# main.net
KiCad netlist of a schematic drawn in EAGLE
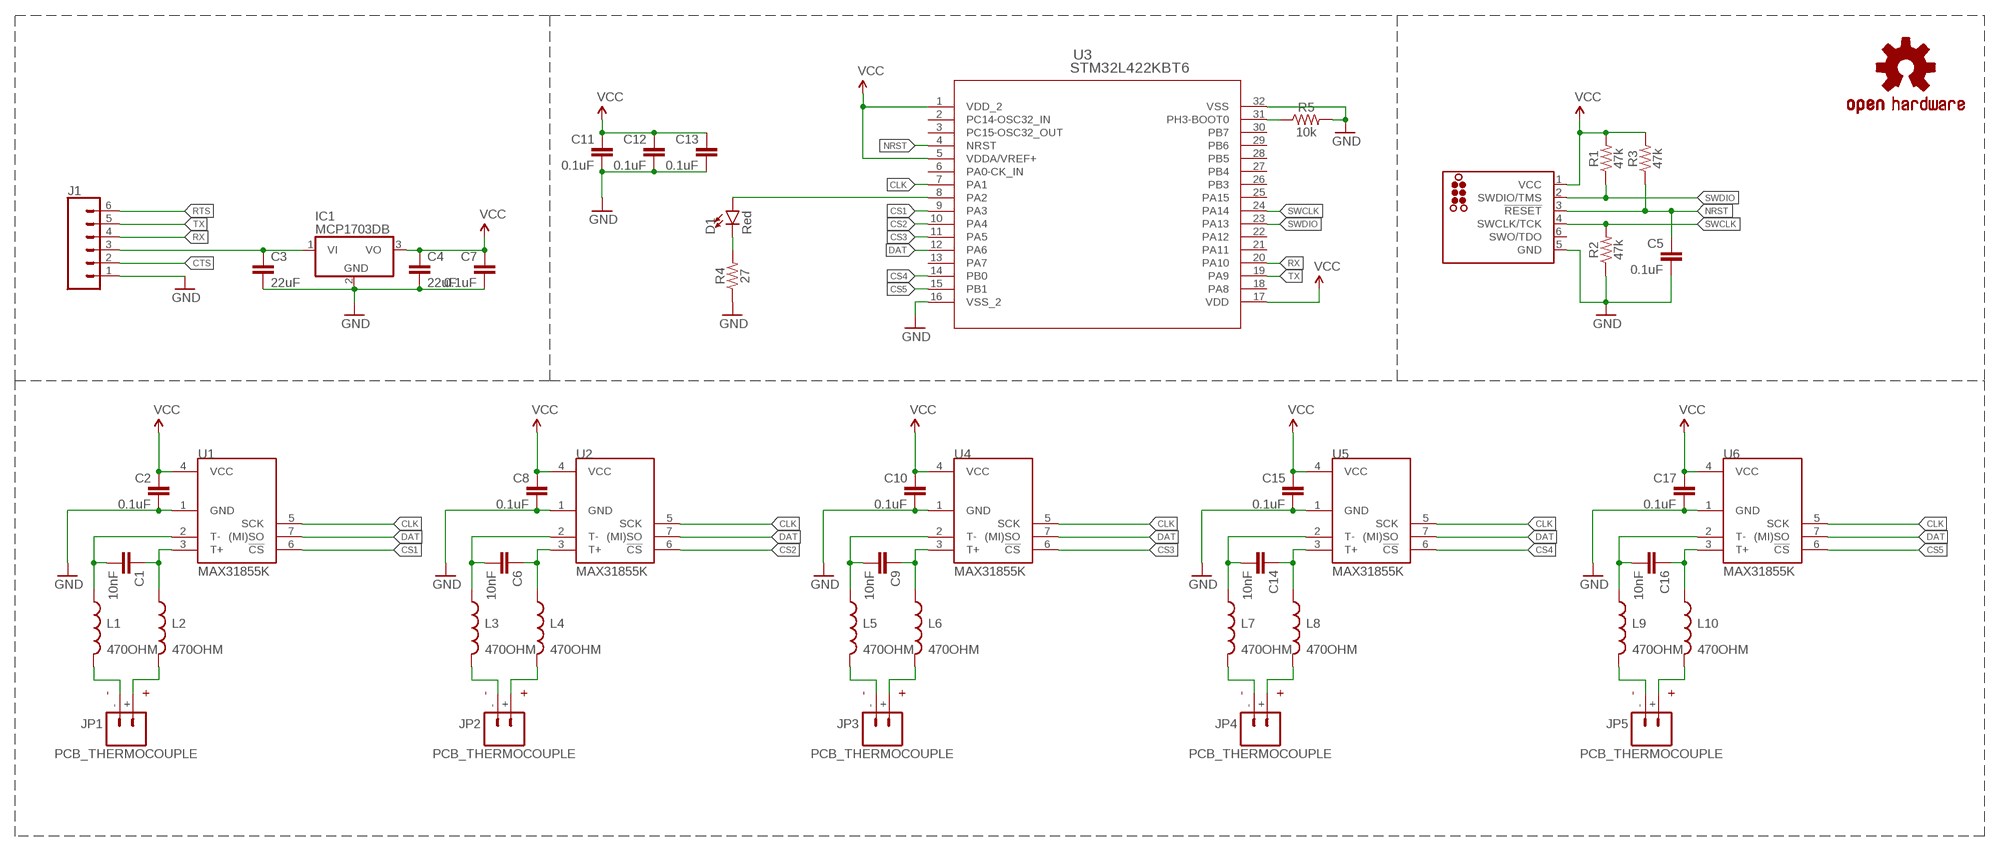
[diagram p0: schematic, sheet 1]

(export (version "E")
  (design (tool "Eeschema 10.0.6"))
  (components
    (comp (ref "C1")
      (value "10nF")
      (footprint "eagle-import:0603-CAP")
      (libsource (lib "eagle-import") (part "10NF/10000PF-50V-10%(0603)"))
    )
    (comp (ref "C2")
      (value "0.1uF")
      (footprint "eagle-import:0603-CAP")
      (libsource (lib "eagle-import") (part "0.1UF-25V(+80/-20%)(0603)"))
    )
    (comp (ref "C3")
      (value "22uF")
      (footprint "eagle-import:0603")
      (libsource (lib "eagle-import") (part "22UF-0603-6.3V-20%"))
    )
    (comp (ref "C4")
      (value "22uF")
      (footprint "eagle-import:0603")
      (libsource (lib "eagle-import") (part "22UF-0603-6.3V-20%"))
    )
    (comp (ref "C5")
      (value "0.1uF")
      (footprint "eagle-import:0603-CAP")
      (libsource (lib "eagle-import") (part "0.1UF-25V(+80/-20%)(0603)"))
    )
    (comp (ref "C6")
      (value "10nF")
      (footprint "eagle-import:0603-CAP")
      (libsource (lib "eagle-import") (part "10NF/10000PF-50V-10%(0603)"))
    )
    (comp (ref "C7")
      (value "0.1uF")
      (footprint "eagle-import:0603-CAP")
      (libsource (lib "eagle-import") (part "0.1UF-25V(+80/-20%)(0603)"))
    )
    (comp (ref "C8")
      (value "0.1uF")
      (footprint "eagle-import:0603-CAP")
      (libsource (lib "eagle-import") (part "0.1UF-25V(+80/-20%)(0603)"))
    )
    (comp (ref "C9")
      (value "10nF")
      (footprint "eagle-import:0603-CAP")
      (libsource (lib "eagle-import") (part "10NF/10000PF-50V-10%(0603)"))
    )
    (comp (ref "C10")
      (value "0.1uF")
      (footprint "eagle-import:0603-CAP")
      (libsource (lib "eagle-import") (part "0.1UF-25V(+80/-20%)(0603)"))
    )
    (comp (ref "C11")
      (value "0.1uF")
      (footprint "eagle-import:0603-CAP")
      (libsource (lib "eagle-import") (part "0.1UF-25V(+80/-20%)(0603)"))
    )
    (comp (ref "C12")
      (value "0.1uF")
      (footprint "eagle-import:0603-CAP")
      (libsource (lib "eagle-import") (part "0.1UF-25V(+80/-20%)(0603)"))
    )
    (comp (ref "C13")
      (value "0.1uF")
      (footprint "eagle-import:0603-CAP")
      (libsource (lib "eagle-import") (part "0.1UF-25V(+80/-20%)(0603)"))
    )
    (comp (ref "C14")
      (value "10nF")
      (footprint "eagle-import:0603-CAP")
      (libsource (lib "eagle-import") (part "10NF/10000PF-50V-10%(0603)"))
    )
    (comp (ref "C15")
      (value "0.1uF")
      (footprint "eagle-import:0603-CAP")
      (libsource (lib "eagle-import") (part "0.1UF-25V(+80/-20%)(0603)"))
    )
    (comp (ref "C16")
      (value "10nF")
      (footprint "eagle-import:0603-CAP")
      (libsource (lib "eagle-import") (part "10NF/10000PF-50V-10%(0603)"))
    )
    (comp (ref "C17")
      (value "0.1uF")
      (footprint "eagle-import:0603-CAP")
      (libsource (lib "eagle-import") (part "0.1UF-25V(+80/-20%)(0603)"))
    )
    (comp (ref "D1")
      (value "Red")
      (footprint "eagle-import:LED-0603")
      (libsource (lib "eagle-import") (part "LED-RED-0603-WE"))
    )
    (comp (ref "IC1")
      (value "MCP1703DB")
      (footprint "eagle-import:SOT223")
      (libsource (lib "eagle-import") (part "MCP1703DB"))
    )
    (comp (ref "J1")
      (value "CONN_06NO_SILK_NO_POP")
      (footprint "eagle-import:1X06_NO_SILK")
      (libsource (lib "eagle-import") (part "CONN_06NO_SILK_NO_POP"))
    )
    (comp (ref "J2")
      (value "TC2030_SWD-MCP-NL")
      (footprint "eagle-import:TC2030-MCP-NL")
      (libsource (lib "eagle-import") (part "TC2030_SWD-MCP-NL"))
    )
    (comp (ref "JP1")
      (value "PCB_THERMOCOUPLE")
      (footprint "eagle-import:PCC-SMP")
      (libsource (lib "eagle-import") (part "PCB_THERMOCOUPLE"))
    )
    (comp (ref "JP2")
      (value "PCB_THERMOCOUPLE")
      (footprint "eagle-import:PCC-SMP")
      (libsource (lib "eagle-import") (part "PCB_THERMOCOUPLE"))
    )
    (comp (ref "JP3")
      (value "PCB_THERMOCOUPLE")
      (footprint "eagle-import:PCC-SMP")
      (libsource (lib "eagle-import") (part "PCB_THERMOCOUPLE"))
    )
    (comp (ref "JP4")
      (value "PCB_THERMOCOUPLE")
      (footprint "eagle-import:PCC-SMP")
      (libsource (lib "eagle-import") (part "PCB_THERMOCOUPLE"))
    )
    (comp (ref "JP5")
      (value "PCB_THERMOCOUPLE")
      (footprint "eagle-import:PCC-SMP")
      (libsource (lib "eagle-import") (part "PCB_THERMOCOUPLE"))
    )
    (comp (ref "L1")
      (value "470OHM")
      (footprint "eagle-import:0603")
      (libsource (lib "eagle-import") (part "INDUCTOR0603"))
    )
    (comp (ref "L2")
      (value "470OHM")
      (footprint "eagle-import:0603")
      (libsource (lib "eagle-import") (part "INDUCTOR0603"))
    )
    (comp (ref "L3")
      (value "470OHM")
      (footprint "eagle-import:0603")
      (libsource (lib "eagle-import") (part "INDUCTOR0603"))
    )
    (comp (ref "L4")
      (value "470OHM")
      (footprint "eagle-import:0603")
      (libsource (lib "eagle-import") (part "INDUCTOR0603"))
    )
    (comp (ref "L5")
      (value "470OHM")
      (footprint "eagle-import:0603")
      (libsource (lib "eagle-import") (part "INDUCTOR0603"))
    )
    (comp (ref "L6")
      (value "470OHM")
      (footprint "eagle-import:0603")
      (libsource (lib "eagle-import") (part "INDUCTOR0603"))
    )
    (comp (ref "L7")
      (value "470OHM")
      (footprint "eagle-import:0603")
      (libsource (lib "eagle-import") (part "INDUCTOR0603"))
    )
    (comp (ref "L8")
      (value "470OHM")
      (footprint "eagle-import:0603")
      (libsource (lib "eagle-import") (part "INDUCTOR0603"))
    )
    (comp (ref "L9")
      (value "470OHM")
      (footprint "eagle-import:0603")
      (libsource (lib "eagle-import") (part "INDUCTOR0603"))
    )
    (comp (ref "L10")
      (value "470OHM")
      (footprint "eagle-import:0603")
      (libsource (lib "eagle-import") (part "INDUCTOR0603"))
    )
    (comp (ref "LOGO1")
      (value "OSHW-LOGOL")
      (footprint "eagle-import:OSHW-LOGO-L")
      (libsource (lib "eagle-import") (part "OSHW-LOGOL"))
    )
    (comp (ref "R1")
      (value "47k")
      (footprint "eagle-import:0603")
      (libsource (lib "eagle-import") (part "47KOHM-0603-1/10W-1%"))
    )
    (comp (ref "R2")
      (value "47k")
      (footprint "eagle-import:0603")
      (libsource (lib "eagle-import") (part "47KOHM-0603-1/10W-1%"))
    )
    (comp (ref "R3")
      (value "47k")
      (footprint "eagle-import:0603")
      (libsource (lib "eagle-import") (part "47KOHM-0603-1/10W-1%"))
    )
    (comp (ref "R4")
      (value "27")
      (footprint "eagle-import:0603")
      (libsource (lib "eagle-import") (part "27OHM-0603-1/10W-1%"))
    )
    (comp (ref "R5")
      (value "10k")
      (footprint "eagle-import:0603")
      (libsource (lib "eagle-import") (part "10KOHM-0603-1/10W-1%"))
    )
    (comp (ref "U1")
      (value "MAX31855K")
      (footprint "eagle-import:SOIC8")
      (libsource (lib "eagle-import") (part "MAX31855K"))
    )
    (comp (ref "U2")
      (value "MAX31855K")
      (footprint "eagle-import:SOIC8")
      (libsource (lib "eagle-import") (part "MAX31855K"))
    )
    (comp (ref "U3")
      (value "STM32L422KBT6")
      (footprint "eagle-import:LQFP_422KBT6_STM")
      (fields (field (name "COPYRIGHT") "Copyright (C) 2023 Ultra Librarian. All rights reserved."))
      (libsource (lib "eagle-import") (part "STM32L422KBT6"))
    )
    (comp (ref "U4")
      (value "MAX31855K")
      (footprint "eagle-import:SOIC8")
      (libsource (lib "eagle-import") (part "MAX31855K"))
    )
    (comp (ref "U5")
      (value "MAX31855K")
      (footprint "eagle-import:SOIC8")
      (libsource (lib "eagle-import") (part "MAX31855K"))
    )
    (comp (ref "U6")
      (value "MAX31855K")
      (footprint "eagle-import:SOIC8")
      (libsource (lib "eagle-import") (part "MAX31855K"))
    )
  )
  (nets
    (net (code "1") (name "CLK") (class "Default")
      (node (ref "U1") (pin "5") (pinfunction "SCK_5") (pintype "bidirectional"))
      (node (ref "U2") (pin "5") (pinfunction "SCK_5") (pintype "bidirectional"))
      (node (ref "U3") (pin "7") (pinfunction "PA1_7") (pintype "bidirectional"))
      (node (ref "U4") (pin "5") (pinfunction "SCK_5") (pintype "bidirectional"))
      (node (ref "U5") (pin "5") (pinfunction "SCK_5") (pintype "bidirectional"))
      (node (ref "U6") (pin "5") (pinfunction "SCK_5") (pintype "bidirectional"))
    )
    (net (code "2") (name "CS1") (class "Default")
      (node (ref "U1") (pin "6") (pinfunction "~{CS}_6") (pintype "bidirectional"))
      (node (ref "U3") (pin "9") (pinfunction "PA3_9") (pintype "bidirectional"))
    )
    (net (code "3") (name "CS2") (class "Default")
      (node (ref "U2") (pin "6") (pinfunction "~{CS}_6") (pintype "bidirectional"))
      (node (ref "U3") (pin "10") (pinfunction "PA4_10") (pintype "bidirectional"))
    )
    (net (code "4") (name "CS3") (class "Default")
      (node (ref "U3") (pin "11") (pinfunction "PA5_11") (pintype "bidirectional"))
      (node (ref "U4") (pin "6") (pinfunction "~{CS}_6") (pintype "bidirectional"))
    )
    (net (code "5") (name "CS4") (class "Default")
      (node (ref "U3") (pin "14") (pinfunction "PB0_14") (pintype "bidirectional"))
      (node (ref "U5") (pin "6") (pinfunction "~{CS}_6") (pintype "bidirectional"))
    )
    (net (code "6") (name "CS5") (class "Default")
      (node (ref "U3") (pin "15") (pinfunction "PB1_15") (pintype "bidirectional"))
      (node (ref "U6") (pin "6") (pinfunction "~{CS}_6") (pintype "bidirectional"))
    )
    (net (code "7") (name "CTS") (class "Default")
      (node (ref "J1") (pin "2") (pinfunction "2_2") (pintype "passive"))
    )
    (net (code "8") (name "DAT") (class "Default")
      (node (ref "U1") (pin "7") (pinfunction "(MI)SO_7") (pintype "bidirectional"))
      (node (ref "U2") (pin "7") (pinfunction "(MI)SO_7") (pintype "bidirectional"))
      (node (ref "U3") (pin "12") (pinfunction "PA6_12") (pintype "bidirectional"))
      (node (ref "U4") (pin "7") (pinfunction "(MI)SO_7") (pintype "bidirectional"))
      (node (ref "U5") (pin "7") (pinfunction "(MI)SO_7") (pintype "bidirectional"))
      (node (ref "U6") (pin "7") (pinfunction "(MI)SO_7") (pintype "bidirectional"))
    )
    (net (code "9") (name "GND") (class "Default")
      (node (ref "C10") (pin "2") (pinfunction "2_2") (pintype "passive"))
      (node (ref "C11") (pin "2") (pinfunction "2_2") (pintype "passive"))
      (node (ref "C12") (pin "2") (pinfunction "2_2") (pintype "passive"))
      (node (ref "C13") (pin "2") (pinfunction "2_2") (pintype "passive"))
      (node (ref "C15") (pin "2") (pinfunction "2_2") (pintype "passive"))
      (node (ref "C17") (pin "2") (pinfunction "2_2") (pintype "passive"))
      (node (ref "C2") (pin "2") (pinfunction "2_2") (pintype "passive"))
      (node (ref "C3") (pin "2") (pinfunction "2_2") (pintype "passive"))
      (node (ref "C4") (pin "2") (pinfunction "2_2") (pintype "passive"))
      (node (ref "C5") (pin "2") (pinfunction "2_2") (pintype "passive"))
      (node (ref "C7") (pin "2") (pinfunction "2_2") (pintype "passive"))
      (node (ref "C8") (pin "2") (pinfunction "2_2") (pintype "passive"))
      (node (ref "IC1") (pin "2") (pinfunction "GND_2") (pintype "passive"))
      (node (ref "J1") (pin "1") (pinfunction "1_1") (pintype "passive"))
      (node (ref "J2") (pin "5") (pinfunction "GND_5") (pintype "passive"))
      (node (ref "R2") (pin "1") (pinfunction "1_1") (pintype "passive"))
      (node (ref "R4") (pin "1") (pinfunction "1_1") (pintype "passive"))
      (node (ref "R5") (pin "2") (pinfunction "2_2") (pintype "passive"))
      (node (ref "U1") (pin "1") (pinfunction "GND_1") (pintype "bidirectional"))
      (node (ref "U2") (pin "1") (pinfunction "GND_1") (pintype "bidirectional"))
      (node (ref "U3") (pin "16") (pinfunction "VSS_2_16") (pintype "passive"))
      (node (ref "U3") (pin "32") (pinfunction "VSS_32") (pintype "passive"))
      (node (ref "U4") (pin "1") (pinfunction "GND_1") (pintype "bidirectional"))
      (node (ref "U5") (pin "1") (pinfunction "GND_1") (pintype "bidirectional"))
      (node (ref "U6") (pin "1") (pinfunction "GND_1") (pintype "bidirectional"))
    )
    (net (code "10") (name "NRST") (class "Default")
      (node (ref "C5") (pin "1") (pinfunction "1_1") (pintype "passive"))
      (node (ref "J2") (pin "3") (pinfunction "~{RESET}_3") (pintype "output"))
      (node (ref "R3") (pin "1") (pinfunction "1_1") (pintype "passive"))
      (node (ref "U3") (pin "4") (pinfunction "NRST_4") (pintype "passive"))
    )
    (net (code "11") (name "Net-(D1-PadC)") (class "Default")
      (node (ref "D1") (pin "C") (pinfunction "C_C") (pintype "passive"))
      (node (ref "R4") (pin "2") (pinfunction "2_2") (pintype "passive"))
    )
    (net (code "12") (name "Net-(IC1-VI)") (class "Default")
      (node (ref "C3") (pin "1") (pinfunction "1_1") (pintype "passive"))
      (node (ref "IC1") (pin "1") (pinfunction "VI_1") (pintype "input"))
      (node (ref "J1") (pin "3") (pinfunction "3_3") (pintype "passive"))
    )
    (net (code "13") (name "Net-(JP1-Pad+)") (class "Default")
      (node (ref "JP1") (pin "+") (pinfunction "+_+") (pintype "passive"))
      (node (ref "L2") (pin "2") (pinfunction "2_2") (pintype "passive"))
    )
    (net (code "14") (name "Net-(JP1-Pad-)") (class "Default")
      (node (ref "JP1") (pin "-") (pinfunction "-_-") (pintype "passive"))
      (node (ref "L1") (pin "2") (pinfunction "2_2") (pintype "passive"))
    )
    (net (code "15") (name "Net-(JP2-Pad+)") (class "Default")
      (node (ref "JP2") (pin "+") (pinfunction "+_+") (pintype "passive"))
      (node (ref "L4") (pin "2") (pinfunction "2_2") (pintype "passive"))
    )
    (net (code "16") (name "Net-(JP2-Pad-)") (class "Default")
      (node (ref "JP2") (pin "-") (pinfunction "-_-") (pintype "passive"))
      (node (ref "L3") (pin "2") (pinfunction "2_2") (pintype "passive"))
    )
    (net (code "17") (name "Net-(JP3-Pad+)") (class "Default")
      (node (ref "JP3") (pin "+") (pinfunction "+_+") (pintype "passive"))
      (node (ref "L6") (pin "2") (pinfunction "2_2") (pintype "passive"))
    )
    (net (code "18") (name "Net-(JP3-Pad-)") (class "Default")
      (node (ref "JP3") (pin "-") (pinfunction "-_-") (pintype "passive"))
      (node (ref "L5") (pin "2") (pinfunction "2_2") (pintype "passive"))
    )
    (net (code "19") (name "Net-(JP4-Pad+)") (class "Default")
      (node (ref "JP4") (pin "+") (pinfunction "+_+") (pintype "passive"))
      (node (ref "L8") (pin "2") (pinfunction "2_2") (pintype "passive"))
    )
    (net (code "20") (name "Net-(JP4-Pad-)") (class "Default")
      (node (ref "JP4") (pin "-") (pinfunction "-_-") (pintype "passive"))
      (node (ref "L7") (pin "2") (pinfunction "2_2") (pintype "passive"))
    )
    (net (code "21") (name "Net-(JP5-Pad+)") (class "Default")
      (node (ref "JP5") (pin "+") (pinfunction "+_+") (pintype "passive"))
      (node (ref "L10") (pin "2") (pinfunction "2_2") (pintype "passive"))
    )
    (net (code "22") (name "Net-(JP5-Pad-)") (class "Default")
      (node (ref "JP5") (pin "-") (pinfunction "-_-") (pintype "passive"))
      (node (ref "L9") (pin "2") (pinfunction "2_2") (pintype "passive"))
    )
    (net (code "23") (name "Net-(U1-T+)") (class "Default")
      (node (ref "C1") (pin "1") (pinfunction "1_1") (pintype "passive"))
      (node (ref "L2") (pin "1") (pinfunction "1_1") (pintype "passive"))
      (node (ref "U1") (pin "3") (pinfunction "T+_3") (pintype "bidirectional"))
    )
    (net (code "24") (name "Net-(U1-T-)") (class "Default")
      (node (ref "C1") (pin "2") (pinfunction "2_2") (pintype "passive"))
      (node (ref "L1") (pin "1") (pinfunction "1_1") (pintype "passive"))
      (node (ref "U1") (pin "2") (pinfunction "T-_2") (pintype "bidirectional"))
    )
    (net (code "25") (name "Net-(U2-T+)") (class "Default")
      (node (ref "C6") (pin "1") (pinfunction "1_1") (pintype "passive"))
      (node (ref "L4") (pin "1") (pinfunction "1_1") (pintype "passive"))
      (node (ref "U2") (pin "3") (pinfunction "T+_3") (pintype "bidirectional"))
    )
    (net (code "26") (name "Net-(U2-T-)") (class "Default")
      (node (ref "C6") (pin "2") (pinfunction "2_2") (pintype "passive"))
      (node (ref "L3") (pin "1") (pinfunction "1_1") (pintype "passive"))
      (node (ref "U2") (pin "2") (pinfunction "T-_2") (pintype "bidirectional"))
    )
    (net (code "27") (name "Net-(U3-PA2)") (class "Default")
      (node (ref "D1") (pin "A") (pinfunction "A_A") (pintype "passive"))
      (node (ref "U3") (pin "8") (pinfunction "PA2_8") (pintype "bidirectional"))
    )
    (net (code "28") (name "Net-(U3-PH3-BOOT0)") (class "Default")
      (node (ref "R5") (pin "1") (pinfunction "1_1") (pintype "passive"))
      (node (ref "U3") (pin "31") (pinfunction "PH3-BOOT0_31") (pintype "passive"))
    )
    (net (code "29") (name "Net-(U4-T+)") (class "Default")
      (node (ref "C9") (pin "1") (pinfunction "1_1") (pintype "passive"))
      (node (ref "L6") (pin "1") (pinfunction "1_1") (pintype "passive"))
      (node (ref "U4") (pin "3") (pinfunction "T+_3") (pintype "bidirectional"))
    )
    (net (code "30") (name "Net-(U4-T-)") (class "Default")
      (node (ref "C9") (pin "2") (pinfunction "2_2") (pintype "passive"))
      (node (ref "L5") (pin "1") (pinfunction "1_1") (pintype "passive"))
      (node (ref "U4") (pin "2") (pinfunction "T-_2") (pintype "bidirectional"))
    )
    (net (code "31") (name "Net-(U5-T+)") (class "Default")
      (node (ref "C14") (pin "1") (pinfunction "1_1") (pintype "passive"))
      (node (ref "L8") (pin "1") (pinfunction "1_1") (pintype "passive"))
      (node (ref "U5") (pin "3") (pinfunction "T+_3") (pintype "bidirectional"))
    )
    (net (code "32") (name "Net-(U5-T-)") (class "Default")
      (node (ref "C14") (pin "2") (pinfunction "2_2") (pintype "passive"))
      (node (ref "L7") (pin "1") (pinfunction "1_1") (pintype "passive"))
      (node (ref "U5") (pin "2") (pinfunction "T-_2") (pintype "bidirectional"))
    )
    (net (code "33") (name "Net-(U6-T+)") (class "Default")
      (node (ref "C16") (pin "1") (pinfunction "1_1") (pintype "passive"))
      (node (ref "L10") (pin "1") (pinfunction "1_1") (pintype "passive"))
      (node (ref "U6") (pin "3") (pinfunction "T+_3") (pintype "bidirectional"))
    )
    (net (code "34") (name "Net-(U6-T-)") (class "Default")
      (node (ref "C16") (pin "2") (pinfunction "2_2") (pintype "passive"))
      (node (ref "L9") (pin "1") (pinfunction "1_1") (pintype "passive"))
      (node (ref "U6") (pin "2") (pinfunction "T-_2") (pintype "bidirectional"))
    )
    (net (code "35") (name "RTS") (class "Default")
      (node (ref "J1") (pin "6") (pinfunction "6_6") (pintype "passive"))
    )
    (net (code "36") (name "RX") (class "Default")
      (node (ref "J1") (pin "4") (pinfunction "4_4") (pintype "passive"))
      (node (ref "U3") (pin "20") (pinfunction "PA10_20") (pintype "bidirectional"))
    )
    (net (code "37") (name "SWCLK") (class "Default")
      (node (ref "J2") (pin "4") (pinfunction "SWCLK/TCK_4") (pintype "output"))
      (node (ref "R2") (pin "2") (pinfunction "2_2") (pintype "passive"))
      (node (ref "U3") (pin "24") (pinfunction "PA14_24") (pintype "bidirectional"))
    )
    (net (code "38") (name "SWDIO") (class "Default")
      (node (ref "J2") (pin "2") (pinfunction "SWDIO/TMS_2") (pintype "bidirectional"))
      (node (ref "R1") (pin "1") (pinfunction "1_1") (pintype "passive"))
      (node (ref "U3") (pin "23") (pinfunction "PA13_23") (pintype "bidirectional"))
    )
    (net (code "39") (name "TX") (class "Default")
      (node (ref "J1") (pin "5") (pinfunction "5_5") (pintype "passive"))
      (node (ref "U3") (pin "19") (pinfunction "PA9_19") (pintype "bidirectional"))
    )
    (net (code "40") (name "VCC") (class "Default")
      (node (ref "C10") (pin "1") (pinfunction "1_1") (pintype "passive"))
      (node (ref "C11") (pin "1") (pinfunction "1_1") (pintype "passive"))
      (node (ref "C12") (pin "1") (pinfunction "1_1") (pintype "passive"))
      (node (ref "C13") (pin "1") (pinfunction "1_1") (pintype "passive"))
      (node (ref "C15") (pin "1") (pinfunction "1_1") (pintype "passive"))
      (node (ref "C17") (pin "1") (pinfunction "1_1") (pintype "passive"))
      (node (ref "C2") (pin "1") (pinfunction "1_1") (pintype "passive"))
      (node (ref "C4") (pin "1") (pinfunction "1_1") (pintype "passive"))
      (node (ref "C7") (pin "1") (pinfunction "1_1") (pintype "passive"))
      (node (ref "C8") (pin "1") (pinfunction "1_1") (pintype "passive"))
      (node (ref "IC1") (pin "3") (pinfunction "VO_3") (pintype "passive"))
      (node (ref "J2") (pin "1") (pinfunction "VCC_1") (pintype "passive"))
      (node (ref "R1") (pin "2") (pinfunction "2_2") (pintype "passive"))
      (node (ref "R3") (pin "2") (pinfunction "2_2") (pintype "passive"))
      (node (ref "U1") (pin "4") (pinfunction "VCC_4") (pintype "bidirectional"))
      (node (ref "U2") (pin "4") (pinfunction "VCC_4") (pintype "bidirectional"))
      (node (ref "U3") (pin "1") (pinfunction "VDD_2_1") (pintype "power_in"))
      (node (ref "U3") (pin "17") (pinfunction "VDD_17") (pintype "power_in"))
      (node (ref "U3") (pin "5") (pinfunction "VDDA/VREF+_5") (pintype "power_in"))
      (node (ref "U4") (pin "4") (pinfunction "VCC_4") (pintype "bidirectional"))
      (node (ref "U5") (pin "4") (pinfunction "VCC_4") (pintype "bidirectional"))
      (node (ref "U6") (pin "4") (pinfunction "VCC_4") (pintype "bidirectional"))
    )
    (net (code "41") (name "unconnected-(J2-SWO{slash}TDO-Pad6)") (class "Default")
      (node (ref "J2") (pin "6") (pinfunction "SWO/TDO_6") (pintype "bidirectional"))
    )
    (net (code "42") (name "unconnected-(U3-PA0-CK_IN-Pad6)") (class "Default")
      (node (ref "U3") (pin "6") (pinfunction "PA0-CK_IN_6") (pintype "bidirectional"))
    )
    (net (code "43") (name "unconnected-(U3-PA7-Pad13)") (class "Default")
      (node (ref "U3") (pin "13") (pinfunction "PA7_13") (pintype "bidirectional"))
    )
    (net (code "44") (name "unconnected-(U3-PA8-Pad18)") (class "Default")
      (node (ref "U3") (pin "18") (pinfunction "PA8_18") (pintype "bidirectional"))
    )
    (net (code "45") (name "unconnected-(U3-PA11-Pad21)") (class "Default")
      (node (ref "U3") (pin "21") (pinfunction "PA11_21") (pintype "bidirectional"))
    )
    (net (code "46") (name "unconnected-(U3-PA12-Pad22)") (class "Default")
      (node (ref "U3") (pin "22") (pinfunction "PA12_22") (pintype "bidirectional"))
    )
    (net (code "47") (name "unconnected-(U3-PA15-Pad25)") (class "Default")
      (node (ref "U3") (pin "25") (pinfunction "PA15_25") (pintype "bidirectional"))
    )
    (net (code "48") (name "unconnected-(U3-PB3-Pad26)") (class "Default")
      (node (ref "U3") (pin "26") (pinfunction "PB3_26") (pintype "bidirectional"))
    )
    (net (code "49") (name "unconnected-(U3-PB4-Pad27)") (class "Default")
      (node (ref "U3") (pin "27") (pinfunction "PB4_27") (pintype "bidirectional"))
    )
    (net (code "50") (name "unconnected-(U3-PB5-Pad28)") (class "Default")
      (node (ref "U3") (pin "28") (pinfunction "PB5_28") (pintype "bidirectional"))
    )
    (net (code "51") (name "unconnected-(U3-PB6-Pad29)") (class "Default")
      (node (ref "U3") (pin "29") (pinfunction "PB6_29") (pintype "bidirectional"))
    )
    (net (code "52") (name "unconnected-(U3-PB7-Pad30)") (class "Default")
      (node (ref "U3") (pin "30") (pinfunction "PB7_30") (pintype "bidirectional"))
    )
    (net (code "53") (name "unconnected-(U3-PC14-OSC32_IN-Pad2)") (class "Default")
      (node (ref "U3") (pin "2") (pinfunction "PC14-OSC32_IN_2") (pintype "bidirectional"))
    )
    (net (code "54") (name "unconnected-(U3-PC15-OSC32_OUT-Pad3)") (class "Default")
      (node (ref "U3") (pin "3") (pinfunction "PC15-OSC32_OUT_3") (pintype "output"))
    )
  )
)
